# ALSW_LED.net
KiCad netlist of a schematic drawn in EAGLE
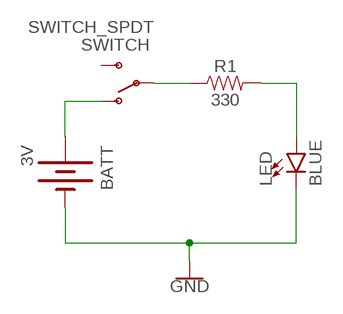
[diagram p0: schematic, sheet 1]

(export (version "E")
  (design (tool "Eeschema 10.0.6"))
  (components
    (comp (ref "BATT")
      (value "3V")
      (footprint "eagle-import:BATTCON_24.5MM")
      (libsource (lib "eagle-import") (part "BATTERY24.5MM"))
    )
    (comp (ref "LED")
      (value "BLUE")
      (footprint "eagle-import:LED-1206")
      (libsource (lib "eagle-import") (part "LED-BLUE1206"))
    )
    (comp (ref "R1")
      (value "330")
      (footprint "eagle-import:0603")
      (libsource (lib "eagle-import") (part "0.27OHM-0603-1/10W-1%"))
    )
    (comp (ref "SWITCH")
      (value "SWITCH_SPDT")
      (footprint "eagle-import:KPS-1290")
      (libsource (lib "eagle-import") (part "SWITCH_SPDT"))
    )
  )
  (nets
    (net (code "1") (name "GND") (class "Default")
      (node (ref "BATT") (pin "2") (pinfunction "-_2") (pintype "power_in"))
      (node (ref "LED") (pin "C") (pinfunction "C_C") (pintype "passive"))
    )
    (net (code "2") (name "Net-(BATT-+)") (class "Default")
      (node (ref "BATT") (pin "1") (pinfunction "+_1") (pintype "power_in"))
      (node (ref "SWITCH") (pin "O") (pinfunction "O_O") (pintype "passive"))
    )
    (net (code "3") (name "Net-(LED-PadA)") (class "Default")
      (node (ref "LED") (pin "A") (pinfunction "A_A") (pintype "passive"))
      (node (ref "R1") (pin "2") (pinfunction "2_2") (pintype "passive"))
    )
    (net (code "4") (name "Net-(R1-Pad1)") (class "Default")
      (node (ref "R1") (pin "1") (pinfunction "1_1") (pintype "passive"))
      (node (ref "SWITCH") (pin "P") (pinfunction "P_P") (pintype "passive"))
    )
    (net (code "5") (name "unconnected-(SWITCH-PadS)") (class "Default")
      (node (ref "SWITCH") (pin "S") (pinfunction "S_S") (pintype "passive"))
    )
  )
)
